# untitled.net
KiCad netlist of a schematic drawn in EAGLE
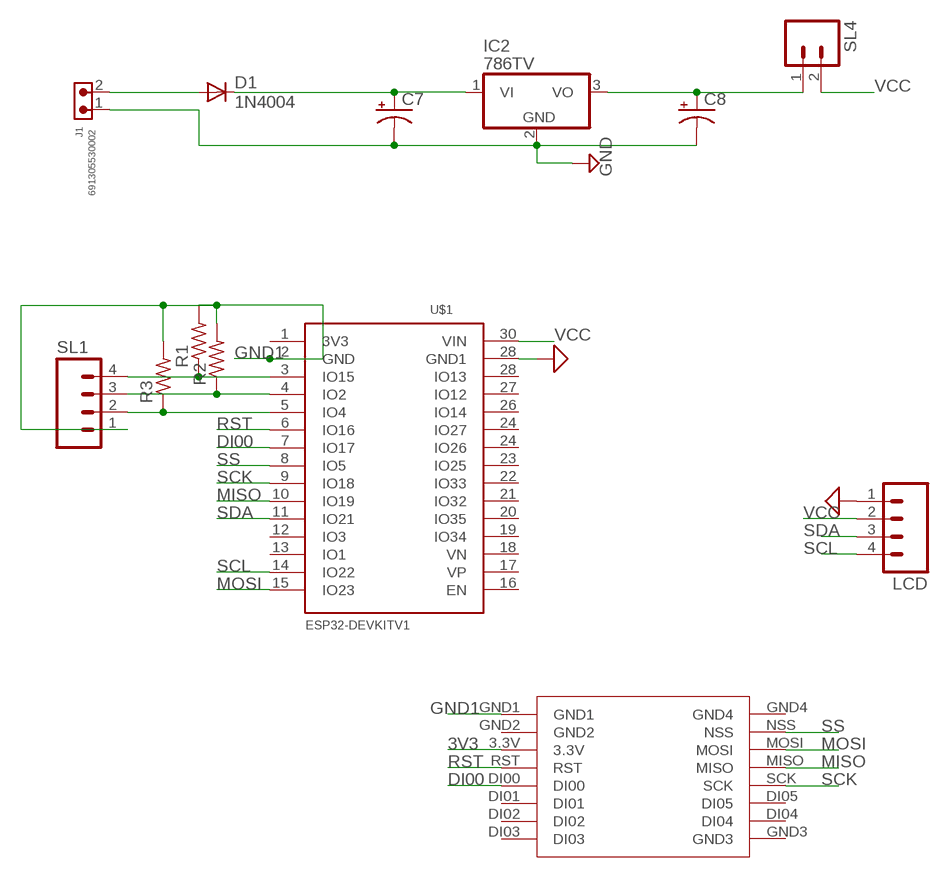
[diagram p0: schematic, sheet 1]

(export (version "E")
  (design (tool "Eeschema 10.0.6"))
  (components
    (comp (ref "C7")
      (value "CAPACITOR-PE5-10.5")
      (footprint "eagle-import:E5-10,5")
      (libsource (lib "eagle-import") (part "CAPACITOR-PE5-10.5"))
    )
    (comp (ref "C8")
      (value "CAPACITOR-PE5-6")
      (footprint "eagle-import:E5-6")
      (libsource (lib "eagle-import") (part "CAPACITOR-PE5-6"))
    )
    (comp (ref "D1")
      (value "1N4004")
      (footprint "eagle-import:DO41-10")
      (libsource (lib "eagle-import") (part "1N4004"))
    )
    (comp (ref "IC2")
      (value "786TV")
      (footprint "eagle-import:TO220V")
      (libsource (lib "eagle-import") (part "78TV6"))
    )
    (comp (ref "J1")
      (value "691305530002")
      (footprint "eagle-import:691305530002")
      (libsource (lib "eagle-import") (part "691305530002"))
    )
    (comp (ref "LCD")
      (value "M04")
      (footprint "eagle-import:04P")
      (libsource (lib "eagle-import") (part "M04"))
    )
    (comp (ref "R1")
      (value "R-US_0207/10")
      (footprint "eagle-import:0207_10")
      (libsource (lib "eagle-import") (part "R-US_0207/10"))
    )
    (comp (ref "R2")
      (value "R-US_0207/10")
      (footprint "eagle-import:0207_10")
      (libsource (lib "eagle-import") (part "R-US_0207/10"))
    )
    (comp (ref "R3")
      (value "R-US_0207/10")
      (footprint "eagle-import:0207_10")
      (libsource (lib "eagle-import") (part "R-US_0207/10"))
    )
    (comp (ref "SL1")
      (value "M04")
      (footprint "eagle-import:04P")
      (libsource (lib "eagle-import") (part "M04"))
    )
    (comp (ref "SL4")
      (value "M02")
      (footprint "eagle-import:02P")
      (libsource (lib "eagle-import") (part "M02"))
    )
    (comp (ref "U$1")
      (value "ESP32DEVKITV1")
      (footprint "eagle-import:ESP32-DEVKITV1")
      (libsource (lib "eagle-import") (part "ESP32DEVKITV1"))
    )
    (comp (ref "U$2")
      (value "LORASX1278")
      (footprint "eagle-import:LORASX1278")
      (libsource (lib "eagle-import") (part "LORASX1278"))
    )
  )
  (nets
    (net (code "1") (name "/3V3") (class "Default")
      (node (ref "U$2") (pin "3.3V") (pinfunction "3.3V_3.3V") (pintype "bidirectional"))
    )
    (net (code "2") (name "/DI00") (class "Default")
      (node (ref "U$1") (pin "7") (pinfunction "IO17_7") (pintype "bidirectional"))
      (node (ref "U$2") (pin "DI00") (pinfunction "DI00_DI00") (pintype "bidirectional"))
    )
    (net (code "3") (name "/GND1") (class "Default")
      (node (ref "R1") (pin "2") (pinfunction "2_2") (pintype "passive"))
      (node (ref "R2") (pin "2") (pinfunction "2_2") (pintype "passive"))
      (node (ref "R3") (pin "2") (pinfunction "2_2") (pintype "passive"))
      (node (ref "SL1") (pin "1") (pinfunction "1_1") (pintype "passive"))
      (node (ref "U$1") (pin "2") (pinfunction "GND_2") (pintype "bidirectional"))
      (node (ref "U$2") (pin "GND1") (pinfunction "GND1_GND1") (pintype "bidirectional"))
    )
    (net (code "4") (name "/MISO") (class "Default")
      (node (ref "U$1") (pin "10") (pinfunction "IO19_10") (pintype "bidirectional"))
      (node (ref "U$2") (pin "MISO") (pinfunction "MISO_MISO") (pintype "bidirectional"))
    )
    (net (code "5") (name "/MOSI") (class "Default")
      (node (ref "U$1") (pin "15") (pinfunction "IO23_15") (pintype "bidirectional"))
      (node (ref "U$2") (pin "MOSI") (pinfunction "MOSI_MOSI") (pintype "bidirectional"))
    )
    (net (code "6") (name "/RST") (class "Default")
      (node (ref "U$1") (pin "6") (pinfunction "IO16_6") (pintype "bidirectional"))
      (node (ref "U$2") (pin "RST") (pinfunction "RST_RST") (pintype "bidirectional"))
    )
    (net (code "7") (name "/SCK") (class "Default")
      (node (ref "U$1") (pin "9") (pinfunction "IO18_9") (pintype "bidirectional"))
      (node (ref "U$2") (pin "SCK") (pinfunction "SCK_SCK") (pintype "bidirectional"))
    )
    (net (code "8") (name "/SCL") (class "Default")
      (node (ref "LCD") (pin "4") (pinfunction "4_4") (pintype "passive"))
      (node (ref "U$1") (pin "14") (pinfunction "IO22_14") (pintype "bidirectional"))
    )
    (net (code "9") (name "/SDA") (class "Default")
      (node (ref "LCD") (pin "3") (pinfunction "3_3") (pintype "passive"))
      (node (ref "U$1") (pin "11") (pinfunction "IO21_11") (pintype "bidirectional"))
    )
    (net (code "10") (name "/SS") (class "Default")
      (node (ref "U$1") (pin "8") (pinfunction "IO5_8") (pintype "bidirectional"))
      (node (ref "U$2") (pin "NSS") (pinfunction "NSS_NSS") (pintype "bidirectional"))
    )
    (net (code "11") (name "/VCC") (class "Default")
      (node (ref "LCD") (pin "2") (pinfunction "2_2") (pintype "passive"))
      (node (ref "SL4") (pin "2") (pinfunction "2_2") (pintype "passive"))
      (node (ref "U$1") (pin "30") (pinfunction "VIN_30") (pintype "bidirectional"))
    )
    (net (code "12") (name "GND") (class "Default")
      (node (ref "C7") (pin "-") (pinfunction "-_-") (pintype "passive"))
      (node (ref "C8") (pin "-") (pinfunction "-_-") (pintype "passive"))
      (node (ref "IC2") (pin "2") (pinfunction "GND_2") (pintype "passive"))
      (node (ref "J1") (pin "1") (pinfunction "1_1") (pintype "passive"))
      (node (ref "LCD") (pin "1") (pinfunction "1_1") (pintype "passive"))
      (node (ref "U$1") (pin "28") (pinfunction "GND1_28") (pintype "bidirectional"))
    )
    (net (code "13") (name "Net-(D1-PadA)") (class "Default")
      (node (ref "D1") (pin "A") (pinfunction "A_A") (pintype "passive"))
      (node (ref "J1") (pin "2") (pinfunction "2_2") (pintype "passive"))
    )
    (net (code "14") (name "Net-(IC2-VI)") (class "Default")
      (node (ref "C7") (pin "+") (pinfunction "+_+") (pintype "passive"))
      (node (ref "D1") (pin "C") (pinfunction "C_C") (pintype "passive"))
      (node (ref "IC2") (pin "1") (pinfunction "VI_1") (pintype "input"))
    )
    (net (code "15") (name "Net-(IC2-VO)") (class "Default")
      (node (ref "C8") (pin "+") (pinfunction "+_+") (pintype "passive"))
      (node (ref "IC2") (pin "3") (pinfunction "VO_3") (pintype "passive"))
      (node (ref "SL4") (pin "1") (pinfunction "1_1") (pintype "passive"))
    )
    (net (code "16") (name "Net-(U$1-IO2)") (class "Default")
      (node (ref "R2") (pin "1") (pinfunction "1_1") (pintype "passive"))
      (node (ref "SL1") (pin "3") (pinfunction "3_3") (pintype "passive"))
      (node (ref "U$1") (pin "4") (pinfunction "IO2_4") (pintype "bidirectional"))
    )
    (net (code "17") (name "Net-(U$1-IO4)") (class "Default")
      (node (ref "R3") (pin "1") (pinfunction "1_1") (pintype "passive"))
      (node (ref "SL1") (pin "2") (pinfunction "2_2") (pintype "passive"))
      (node (ref "U$1") (pin "5") (pinfunction "IO4_5") (pintype "bidirectional"))
    )
    (net (code "18") (name "Net-(U$1-IO15)") (class "Default")
      (node (ref "R1") (pin "1") (pinfunction "1_1") (pintype "passive"))
      (node (ref "SL1") (pin "4") (pinfunction "4_4") (pintype "passive"))
      (node (ref "U$1") (pin "3") (pinfunction "IO15_3") (pintype "bidirectional"))
    )
    (net (code "19") (name "unconnected-(U$1-3V3-Pad1)") (class "Default")
      (node (ref "U$1") (pin "1") (pinfunction "3V3_1") (pintype "bidirectional"))
    )
    (net (code "20") (name "unconnected-(U$1-EN-Pad16)") (class "Default")
      (node (ref "U$1") (pin "16") (pinfunction "EN_16") (pintype "bidirectional"))
    )
    (net (code "21") (name "unconnected-(U$1-IO1-Pad13)") (class "Default")
      (node (ref "U$1") (pin "13") (pinfunction "IO1_13") (pintype "bidirectional"))
    )
    (net (code "22") (name "unconnected-(U$1-IO3-Pad12)") (class "Default")
      (node (ref "U$1") (pin "12") (pinfunction "IO3_12") (pintype "bidirectional"))
    )
    (net (code "23") (name "unconnected-(U$1-IO12-Pad27)") (class "Default")
      (node (ref "U$1") (pin "27") (pinfunction "IO12_27") (pintype "bidirectional"))
    )
    (net (code "24") (name "unconnected-(U$1-IO13-Pad28)") (class "Default")
      (node (ref "U$1") (pin "28") (pinfunction "IO13_28") (pintype "bidirectional"))
    )
    (net (code "25") (name "unconnected-(U$1-IO14-Pad26)") (class "Default")
      (node (ref "U$1") (pin "26") (pinfunction "IO14_26") (pintype "bidirectional"))
    )
    (net (code "26") (name "unconnected-(U$1-IO25-Pad23)") (class "Default")
      (node (ref "U$1") (pin "23") (pinfunction "IO25_23") (pintype "bidirectional"))
    )
    (net (code "27") (name "unconnected-(U$1-IO26-Pad24)") (class "Default")
      (node (ref "U$1") (pin "24") (pinfunction "IO26_24") (pintype "bidirectional"))
    )
    (net (code "28") (name "unconnected-(U$1-IO27-Pad24)") (class "Default")
      (node (ref "U$1") (pin "24") (pinfunction "IO27_24") (pintype "bidirectional"))
    )
    (net (code "29") (name "unconnected-(U$1-IO32-Pad21)") (class "Default")
      (node (ref "U$1") (pin "21") (pinfunction "IO32_21") (pintype "bidirectional"))
    )
    (net (code "30") (name "unconnected-(U$1-IO33-Pad22)") (class "Default")
      (node (ref "U$1") (pin "22") (pinfunction "IO33_22") (pintype "bidirectional"))
    )
    (net (code "31") (name "unconnected-(U$1-IO34-Pad19)") (class "Default")
      (node (ref "U$1") (pin "19") (pinfunction "IO34_19") (pintype "bidirectional"))
    )
    (net (code "32") (name "unconnected-(U$1-IO35-Pad20)") (class "Default")
      (node (ref "U$1") (pin "20") (pinfunction "IO35_20") (pintype "bidirectional"))
    )
    (net (code "33") (name "unconnected-(U$1-VN-Pad18)") (class "Default")
      (node (ref "U$1") (pin "18") (pinfunction "VN_18") (pintype "bidirectional"))
    )
    (net (code "34") (name "unconnected-(U$1-VP-Pad17)") (class "Default")
      (node (ref "U$1") (pin "17") (pinfunction "VP_17") (pintype "bidirectional"))
    )
    (net (code "35") (name "unconnected-(U$2-PadDI01)") (class "Default")
      (node (ref "U$2") (pin "DI01") (pinfunction "DI01_DI01") (pintype "bidirectional"))
    )
    (net (code "36") (name "unconnected-(U$2-PadDI02)") (class "Default")
      (node (ref "U$2") (pin "DI02") (pinfunction "DI02_DI02") (pintype "bidirectional"))
    )
    (net (code "37") (name "unconnected-(U$2-PadDI03)") (class "Default")
      (node (ref "U$2") (pin "DI03") (pinfunction "DI03_DI03") (pintype "bidirectional"))
    )
    (net (code "38") (name "unconnected-(U$2-PadDI04)") (class "Default")
      (node (ref "U$2") (pin "DI04") (pinfunction "DI04_DI04") (pintype "bidirectional"))
    )
    (net (code "39") (name "unconnected-(U$2-PadDI05)") (class "Default")
      (node (ref "U$2") (pin "DI05") (pinfunction "DI05_DI05") (pintype "bidirectional"))
    )
    (net (code "40") (name "unconnected-(U$2-PadGND2)") (class "Default")
      (node (ref "U$2") (pin "GND2") (pinfunction "GND2_GND2") (pintype "bidirectional"))
    )
    (net (code "41") (name "unconnected-(U$2-PadGND3)") (class "Default")
      (node (ref "U$2") (pin "GND3") (pinfunction "GND3_GND3") (pintype "bidirectional"))
    )
    (net (code "42") (name "unconnected-(U$2-PadGND4)") (class "Default")
      (node (ref "U$2") (pin "GND4") (pinfunction "GND4_GND4") (pintype "bidirectional"))
    )
  )
)
